# rapidshark-main-breakout-top-mk-1_C.net
KiCad netlist of a schematic drawn in EAGLE
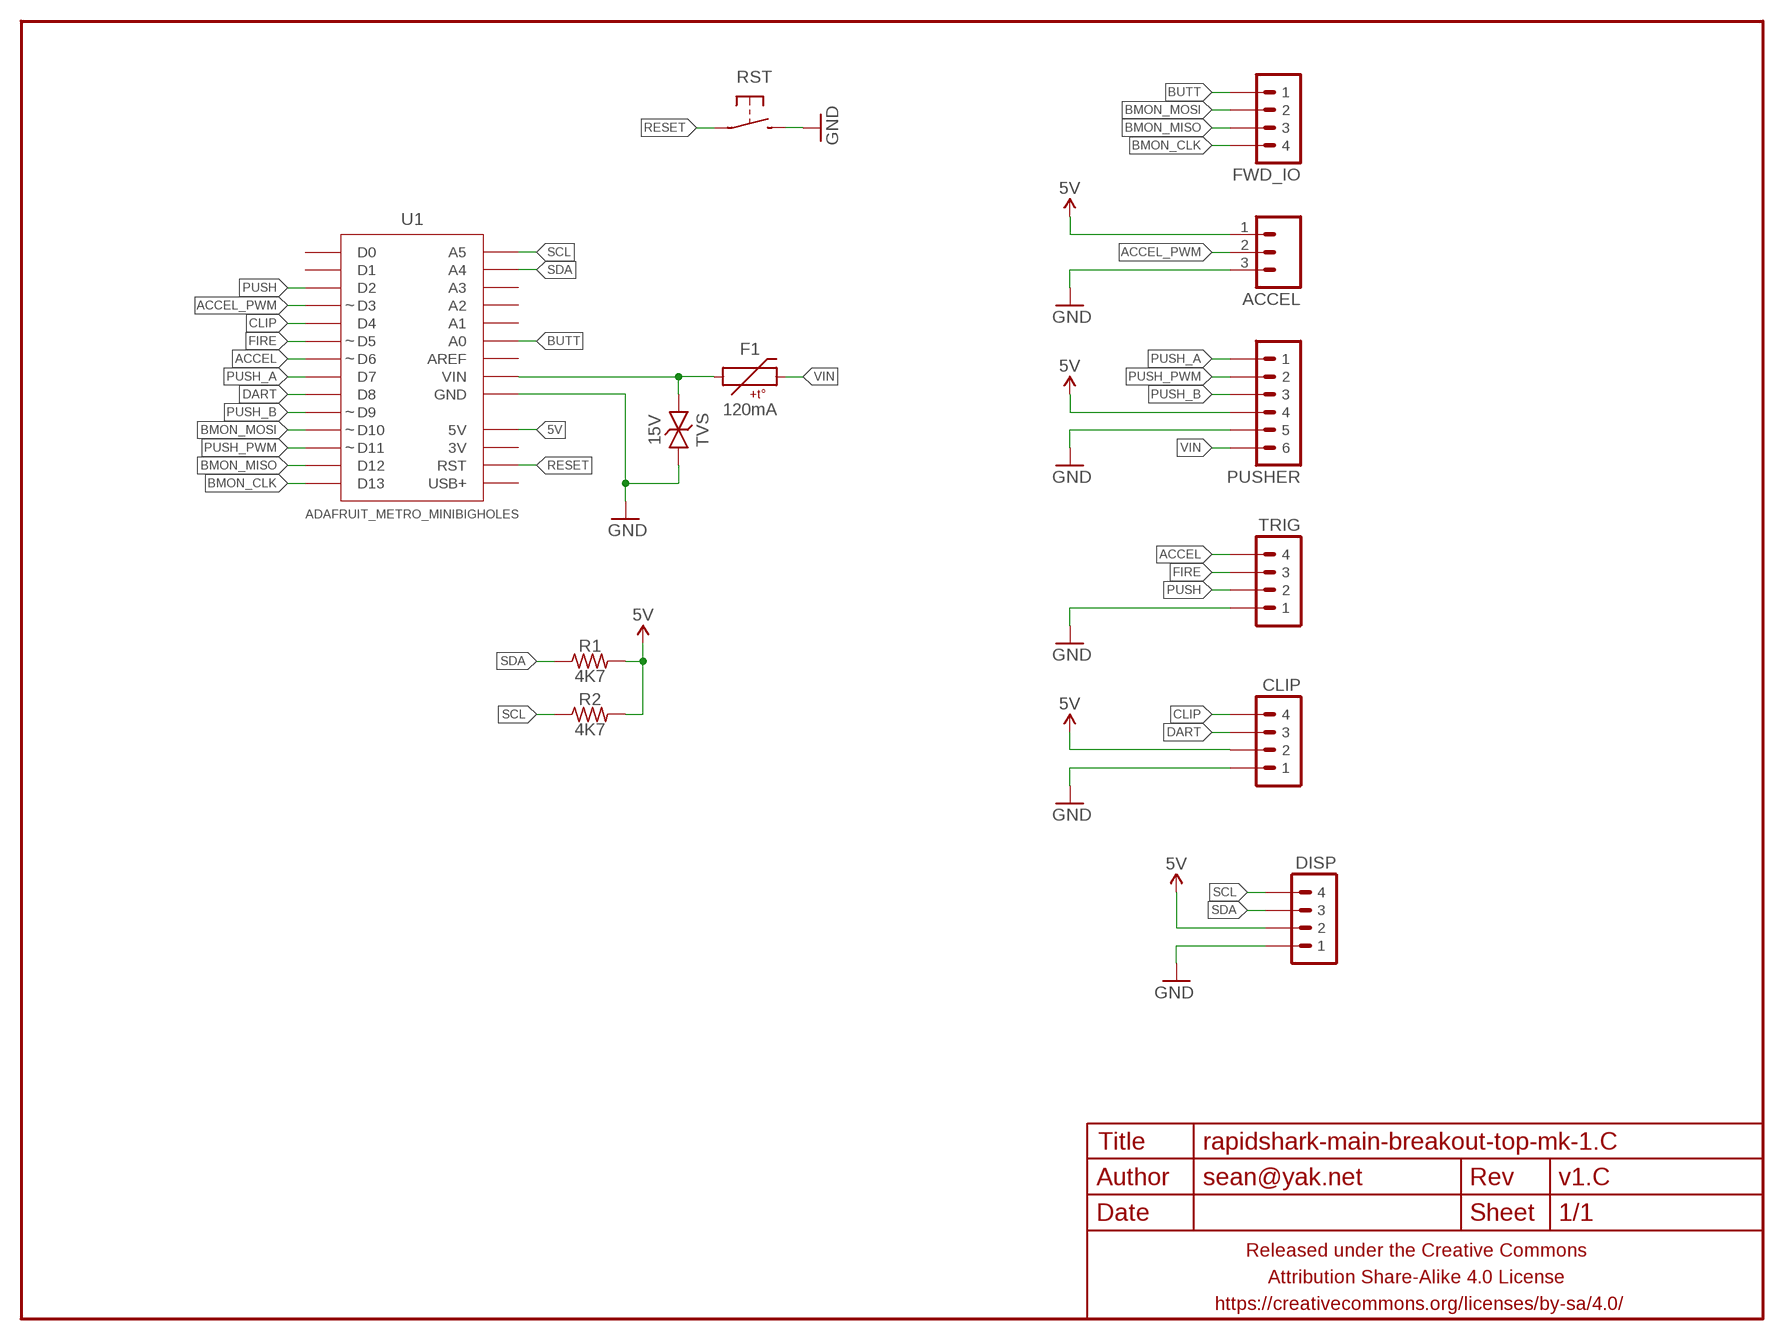
[diagram p0: schematic, sheet 1]

(export (version "E")
  (design (tool "Eeschema 10.0.6"))
  (components
    (comp (ref "ACCEL")
      (value "M03JST-PTH-VERT-CENTERED")
      (footprint "eagle-import:JST-3-PH-VERT-PTH-CENTERED")
      (libsource (lib "eagle-import") (part "M03JST-PTH-VERT-CENTERED"))
    )
    (comp (ref "CLIP")
      (value "M04JST-PTH-VERT")
      (footprint "eagle-import:JST-4-PH-VERT-PTH")
      (libsource (lib "eagle-import") (part "M04JST-PTH-VERT"))
    )
    (comp (ref "DISP")
      (value "M04JST-PTH-VERT")
      (footprint "eagle-import:JST-4-PH-VERT-PTH")
      (libsource (lib "eagle-import") (part "M04JST-PTH-VERT"))
    )
    (comp (ref "F1")
      (value "120mA")
      (footprint "eagle-import:PTC-1206")
      (libsource (lib "eagle-import") (part "PTCSMD"))
    )
    (comp (ref "FRAME1")
      (value "FRAME-LETTERNO_PACKAGE")
      (footprint "eagle-import:DUMMY")
      (fields (field (name "DESIGNER") "sean@yak.net") (field (name "VERSION") "v1.C"))
      (libsource (lib "eagle-import") (part "FRAME-LETTERNO_PACKAGE"))
    )
    (comp (ref "FWD_IO")
      (value "M04JST-PTH-VERT")
      (footprint "eagle-import:JST-4-PH-VERT-PTH")
      (libsource (lib "eagle-import") (part "M04JST-PTH-VERT"))
    )
    (comp (ref "PUSHER")
      (value "M06JST-PH-PTH-VERT")
      (footprint "eagle-import:JST-6-PH-VERT-PTH")
      (libsource (lib "eagle-import") (part "M06JST-PH-PTH-VERT"))
    )
    (comp (ref "R1")
      (value "4K7")
      (footprint "eagle-import:R0603-TIGHTER")
      (libsource (lib "eagle-import") (part "RESISTORR0603-TIGHTER"))
    )
    (comp (ref "R2")
      (value "4K7")
      (footprint "eagle-import:R0603-TIGHTER")
      (libsource (lib "eagle-import") (part "RESISTORR0603-TIGHTER"))
    )
    (comp (ref "RST")
      (value "SPST-NO-TACTCK-PTS840-GK")
      (footprint "eagle-import:TACTILE-SMD-CK-PTS840-GK")
      (libsource (lib "eagle-import") (part "SPST-NO-TACTCK-PTS840-GK"))
    )
    (comp (ref "TRIG")
      (value "M04JST-PTH-VERT")
      (footprint "eagle-import:JST-4-PH-VERT-PTH")
      (libsource (lib "eagle-import") (part "M04JST-PTH-VERT"))
    )
    (comp (ref "TVS")
      (value "15V")
      (footprint "eagle-import:SMA-DIODE-TVS-BIDIR")
      (libsource (lib "eagle-import") (part "TVSSMA"))
    )
    (comp (ref "U1")
      (value "ADAFRUIT_METRO_MINIBIGHOLES")
      (footprint "eagle-import:ADAFRUIT_METRO_MINI_BIGHOLES")
      (libsource (lib "eagle-import") (part "ADAFRUIT_METRO_MINIBIGHOLES"))
    )
  )
  (nets
    (net (code "1") (name "5V") (class "Default")
      (node (ref "ACCEL") (pin "1") (pinfunction "1_1") (pintype "passive"))
      (node (ref "CLIP") (pin "2") (pinfunction "2_2") (pintype "passive"))
      (node (ref "DISP") (pin "2") (pinfunction "2_2") (pintype "passive"))
      (node (ref "PUSHER") (pin "4") (pinfunction "4_4") (pintype "passive"))
      (node (ref "R1") (pin "2") (pinfunction "2_2") (pintype "passive"))
      (node (ref "R2") (pin "2") (pinfunction "2_2") (pintype "passive"))
      (node (ref "U1") (pin "18") (pinfunction "5V_18") (pintype "bidirectional"))
    )
    (net (code "2") (name "ACCEL") (class "Default")
      (node (ref "TRIG") (pin "4") (pinfunction "4_4") (pintype "passive"))
      (node (ref "U1") (pin "7") (pinfunction "D6_7") (pintype "bidirectional"))
    )
    (net (code "3") (name "ACCEL_PWM") (class "Default")
      (node (ref "ACCEL") (pin "2") (pinfunction "2_2") (pintype "passive"))
      (node (ref "U1") (pin "4") (pinfunction "D3_4") (pintype "bidirectional"))
    )
    (net (code "4") (name "BMON_CLK") (class "Default")
      (node (ref "FWD_IO") (pin "4") (pinfunction "4_4") (pintype "passive"))
      (node (ref "U1") (pin "14") (pinfunction "D13_14") (pintype "bidirectional"))
    )
    (net (code "5") (name "BMON_MISO") (class "Default")
      (node (ref "FWD_IO") (pin "3") (pinfunction "3_3") (pintype "passive"))
      (node (ref "U1") (pin "13") (pinfunction "D12_13") (pintype "bidirectional"))
    )
    (net (code "6") (name "BMON_MOSI") (class "Default")
      (node (ref "FWD_IO") (pin "2") (pinfunction "2_2") (pintype "passive"))
      (node (ref "U1") (pin "11") (pinfunction "D10_11") (pintype "bidirectional"))
    )
    (net (code "7") (name "BUTT") (class "Default")
      (node (ref "FWD_IO") (pin "1") (pinfunction "1_1") (pintype "passive"))
      (node (ref "U1") (pin "23") (pinfunction "A0_23") (pintype "bidirectional"))
    )
    (net (code "8") (name "CLIP") (class "Default")
      (node (ref "CLIP") (pin "4") (pinfunction "4_4") (pintype "passive"))
      (node (ref "U1") (pin "5") (pinfunction "D4_5") (pintype "bidirectional"))
    )
    (net (code "9") (name "DART") (class "Default")
      (node (ref "CLIP") (pin "3") (pinfunction "3_3") (pintype "passive"))
      (node (ref "U1") (pin "9") (pinfunction "D8_9") (pintype "bidirectional"))
    )
    (net (code "10") (name "FIRE") (class "Default")
      (node (ref "TRIG") (pin "3") (pinfunction "3_3") (pintype "passive"))
      (node (ref "U1") (pin "6") (pinfunction "D5_6") (pintype "bidirectional"))
    )
    (net (code "11") (name "GND") (class "Default")
      (node (ref "ACCEL") (pin "3") (pinfunction "3_3") (pintype "passive"))
      (node (ref "CLIP") (pin "1") (pinfunction "1_1") (pintype "passive"))
      (node (ref "DISP") (pin "1") (pinfunction "1_1") (pintype "passive"))
      (node (ref "PUSHER") (pin "5") (pinfunction "5_5") (pintype "passive"))
      (node (ref "RST") (pin "3") (pinfunction "2_3") (pintype "passive"))
      (node (ref "RST") (pin "4") (pinfunction "2_4") (pintype "passive"))
      (node (ref "TRIG") (pin "1") (pinfunction "1_1") (pintype "passive"))
      (node (ref "TVS") (pin "1") (pinfunction "1_1") (pintype "passive"))
      (node (ref "U1") (pin "19") (pinfunction "GND_19") (pintype "bidirectional"))
      (node (ref "U1") (pin "20") (pinfunction "GND_20") (pintype "bidirectional"))
    )
    (net (code "12") (name "Net-(U1-VIN)") (class "Default")
      (node (ref "F1") (pin "1") (pinfunction "1_1") (pintype "passive"))
      (node (ref "TVS") (pin "2") (pinfunction "2_2") (pintype "passive"))
      (node (ref "U1") (pin "21") (pinfunction "VIN_21") (pintype "bidirectional"))
    )
    (net (code "13") (name "PUSH") (class "Default")
      (node (ref "TRIG") (pin "2") (pinfunction "2_2") (pintype "passive"))
      (node (ref "U1") (pin "3") (pinfunction "D2_3") (pintype "bidirectional"))
    )
    (net (code "14") (name "PUSH_A") (class "Default")
      (node (ref "PUSHER") (pin "1") (pinfunction "1_1") (pintype "passive"))
      (node (ref "U1") (pin "8") (pinfunction "D7_8") (pintype "bidirectional"))
    )
    (net (code "15") (name "PUSH_B") (class "Default")
      (node (ref "PUSHER") (pin "3") (pinfunction "3_3") (pintype "passive"))
      (node (ref "U1") (pin "10") (pinfunction "D9_10") (pintype "bidirectional"))
    )
    (net (code "16") (name "PUSH_PWM") (class "Default")
      (node (ref "PUSHER") (pin "2") (pinfunction "2_2") (pintype "passive"))
      (node (ref "U1") (pin "12") (pinfunction "D11_12") (pintype "bidirectional"))
    )
    (net (code "17") (name "RESET") (class "Default")
      (node (ref "RST") (pin "1") (pinfunction "1_1") (pintype "passive"))
      (node (ref "RST") (pin "2") (pinfunction "1_2") (pintype "passive"))
      (node (ref "U1") (pin "16") (pinfunction "RST_16") (pintype "bidirectional"))
    )
    (net (code "18") (name "SCL") (class "Default")
      (node (ref "DISP") (pin "4") (pinfunction "4_4") (pintype "passive"))
      (node (ref "R2") (pin "1") (pinfunction "1_1") (pintype "passive"))
      (node (ref "U1") (pin "28") (pinfunction "A5_28") (pintype "bidirectional"))
    )
    (net (code "19") (name "SDA") (class "Default")
      (node (ref "DISP") (pin "3") (pinfunction "3_3") (pintype "passive"))
      (node (ref "R1") (pin "1") (pinfunction "1_1") (pintype "passive"))
      (node (ref "U1") (pin "27") (pinfunction "A4_27") (pintype "bidirectional"))
    )
    (net (code "20") (name "VIN") (class "Default")
      (node (ref "F1") (pin "2") (pinfunction "2_2") (pintype "passive"))
      (node (ref "PUSHER") (pin "6") (pinfunction "6_6") (pintype "passive"))
    )
    (net (code "21") (name "unconnected-(U1-3V-Pad17)") (class "Default")
      (node (ref "U1") (pin "17") (pinfunction "3V_17") (pintype "bidirectional"))
    )
    (net (code "22") (name "unconnected-(U1-A1-Pad24)") (class "Default")
      (node (ref "U1") (pin "24") (pinfunction "A1_24") (pintype "bidirectional"))
    )
    (net (code "23") (name "unconnected-(U1-A2-Pad25)") (class "Default")
      (node (ref "U1") (pin "25") (pinfunction "A2_25") (pintype "bidirectional"))
    )
    (net (code "24") (name "unconnected-(U1-A3-Pad26)") (class "Default")
      (node (ref "U1") (pin "26") (pinfunction "A3_26") (pintype "bidirectional"))
    )
    (net (code "25") (name "unconnected-(U1-AREF-Pad22)") (class "Default")
      (node (ref "U1") (pin "22") (pinfunction "AREF_22") (pintype "bidirectional"))
    )
    (net (code "26") (name "unconnected-(U1-D0-Pad1)") (class "Default")
      (node (ref "U1") (pin "1") (pinfunction "D0_1") (pintype "bidirectional"))
    )
    (net (code "27") (name "unconnected-(U1-D1-Pad2)") (class "Default")
      (node (ref "U1") (pin "2") (pinfunction "D1_2") (pintype "bidirectional"))
    )
    (net (code "28") (name "unconnected-(U1-USB+-Pad15)") (class "Default")
      (node (ref "U1") (pin "15") (pinfunction "USB+_15") (pintype "bidirectional"))
    )
  )
)
